# AP_AT42QT2120.net
KiCad netlist of a schematic drawn in EAGLE
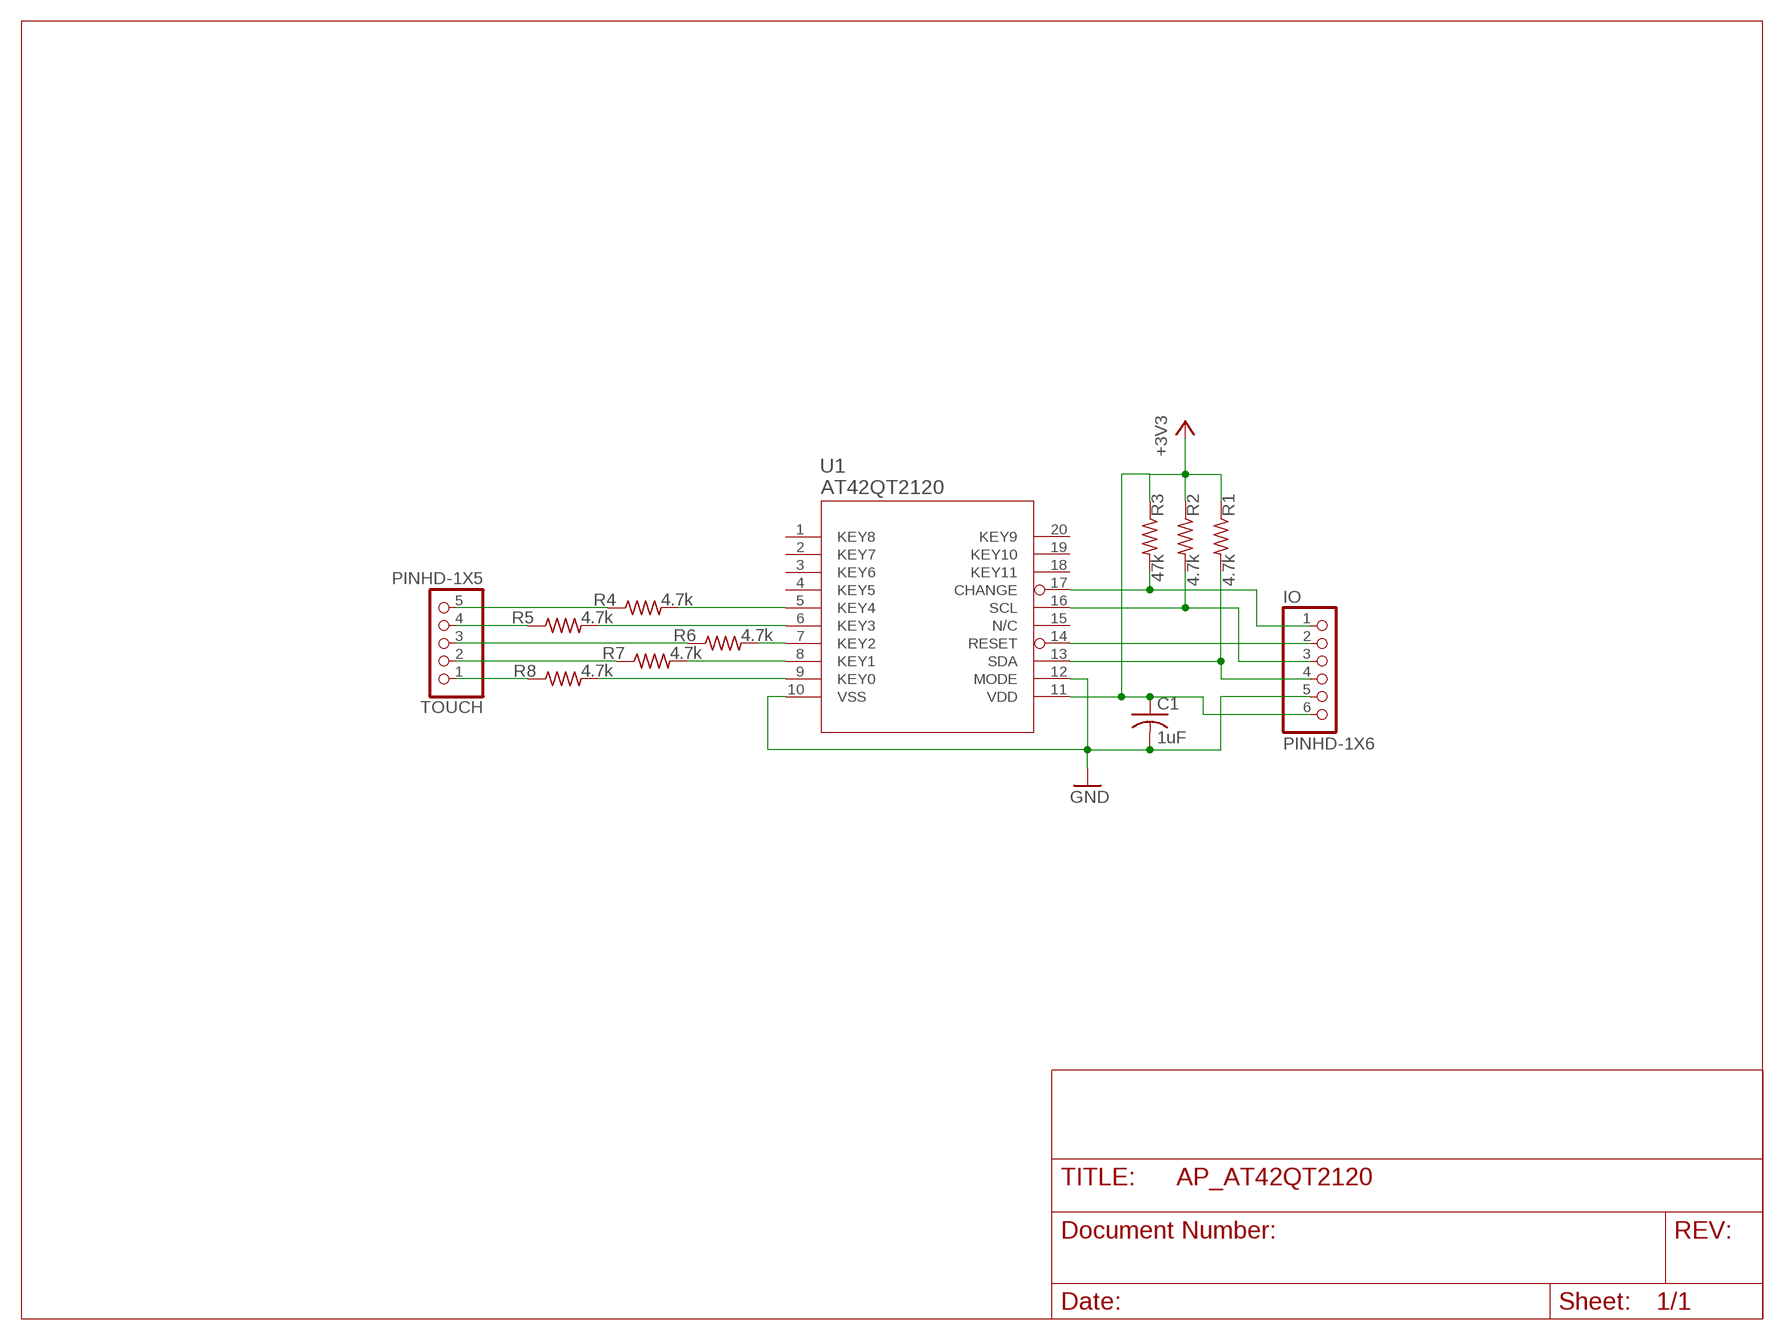
[diagram p0: schematic, sheet 1]

(export (version "E")
  (design (tool "Eeschema 10.0.6"))
  (components
    (comp (ref "C1")
      (value "1uF")
      (footprint "eagle-import:C1206")
      (libsource (lib "eagle-import") (part "C-USC1206"))
    )
    (comp (ref "IO")
      (value "PINHD-1X6")
      (footprint "eagle-import:1X06")
      (libsource (lib "eagle-import") (part "PINHD-1X6"))
    )
    (comp (ref "R1")
      (value "4.7k")
      (footprint "eagle-import:R1206")
      (libsource (lib "eagle-import") (part "R-US_R1206"))
    )
    (comp (ref "R2")
      (value "4.7k")
      (footprint "eagle-import:R1206")
      (libsource (lib "eagle-import") (part "R-US_R1206"))
    )
    (comp (ref "R3")
      (value "47k")
      (footprint "eagle-import:R1206")
      (libsource (lib "eagle-import") (part "R-US_R1206"))
    )
    (comp (ref "R4")
      (value "4.7k")
      (footprint "eagle-import:R1206")
      (libsource (lib "eagle-import") (part "R-US_R1206"))
    )
    (comp (ref "R5")
      (value "4.7k")
      (footprint "eagle-import:R1206")
      (libsource (lib "eagle-import") (part "R-US_R1206"))
    )
    (comp (ref "R6")
      (value "4.7k")
      (footprint "eagle-import:R1206")
      (libsource (lib "eagle-import") (part "R-US_R1206"))
    )
    (comp (ref "R7")
      (value "4.7k")
      (footprint "eagle-import:R1206")
      (libsource (lib "eagle-import") (part "R-US_R1206"))
    )
    (comp (ref "R8")
      (value "4.7k")
      (footprint "eagle-import:R1206")
      (libsource (lib "eagle-import") (part "R-US_R1206"))
    )
    (comp (ref "TOUCH")
      (value "PINHD-1X5")
      (footprint "eagle-import:1X05")
      (libsource (lib "eagle-import") (part "PINHD-1X5"))
    )
    (comp (ref "U1")
      (value "AT42QT2120")
      (footprint "eagle-import:SOIC20")
      (libsource (lib "eagle-import") (part "AT42QT2120-SU"))
    )
  )
  (nets
    (net (code "1") (name "+3V3") (class "Default")
      (node (ref "C1") (pin "1") (pinfunction "1_1") (pintype "passive"))
      (node (ref "IO") (pin "6") (pinfunction "6_6") (pintype "passive"))
      (node (ref "R1") (pin "1") (pinfunction "1_1") (pintype "passive"))
      (node (ref "R2") (pin "1") (pinfunction "1_1") (pintype "passive"))
      (node (ref "R3") (pin "1") (pinfunction "1_1") (pintype "passive"))
      (node (ref "U1") (pin "11") (pinfunction "VDD_11") (pintype "power_in"))
    )
    (net (code "2") (name "GND") (class "Default")
      (node (ref "C1") (pin "2") (pinfunction "2_2") (pintype "passive"))
      (node (ref "IO") (pin "5") (pinfunction "5_5") (pintype "passive"))
      (node (ref "U1") (pin "10") (pinfunction "VSS_10") (pintype "passive"))
      (node (ref "U1") (pin "12") (pinfunction "MODE_12") (pintype "passive"))
    )
    (net (code "3") (name "Net-(R4-Pad1)") (class "Default")
      (node (ref "R4") (pin "1") (pinfunction "1_1") (pintype "passive"))
      (node (ref "TOUCH") (pin "5") (pinfunction "5_5") (pintype "passive"))
    )
    (net (code "4") (name "Net-(R5-Pad1)") (class "Default")
      (node (ref "R5") (pin "1") (pinfunction "1_1") (pintype "passive"))
      (node (ref "TOUCH") (pin "4") (pinfunction "4_4") (pintype "passive"))
    )
    (net (code "5") (name "Net-(R6-Pad1)") (class "Default")
      (node (ref "R6") (pin "1") (pinfunction "1_1") (pintype "passive"))
      (node (ref "TOUCH") (pin "3") (pinfunction "3_3") (pintype "passive"))
    )
    (net (code "6") (name "Net-(R7-Pad1)") (class "Default")
      (node (ref "R7") (pin "1") (pinfunction "1_1") (pintype "passive"))
      (node (ref "TOUCH") (pin "2") (pinfunction "2_2") (pintype "passive"))
    )
    (net (code "7") (name "Net-(R8-Pad1)") (class "Default")
      (node (ref "R8") (pin "1") (pinfunction "1_1") (pintype "passive"))
      (node (ref "TOUCH") (pin "1") (pinfunction "1_1") (pintype "passive"))
    )
    (net (code "8") (name "Net-(U1-CHANGE)") (class "Default")
      (node (ref "IO") (pin "1") (pinfunction "1_1") (pintype "passive"))
      (node (ref "R3") (pin "2") (pinfunction "2_2") (pintype "passive"))
      (node (ref "U1") (pin "17") (pinfunction "CHANGE_17") (pintype "input"))
    )
    (net (code "9") (name "Net-(U1-KEY0)") (class "Default")
      (node (ref "R8") (pin "2") (pinfunction "2_2") (pintype "passive"))
      (node (ref "U1") (pin "9") (pinfunction "KEY0_9") (pintype "bidirectional"))
    )
    (net (code "10") (name "Net-(U1-KEY1)") (class "Default")
      (node (ref "R7") (pin "2") (pinfunction "2_2") (pintype "passive"))
      (node (ref "U1") (pin "8") (pinfunction "KEY1_8") (pintype "bidirectional"))
    )
    (net (code "11") (name "Net-(U1-KEY2)") (class "Default")
      (node (ref "R6") (pin "2") (pinfunction "2_2") (pintype "passive"))
      (node (ref "U1") (pin "7") (pinfunction "KEY2_7") (pintype "bidirectional"))
    )
    (net (code "12") (name "Net-(U1-KEY3)") (class "Default")
      (node (ref "R5") (pin "2") (pinfunction "2_2") (pintype "passive"))
      (node (ref "U1") (pin "6") (pinfunction "KEY3_6") (pintype "bidirectional"))
    )
    (net (code "13") (name "Net-(U1-KEY4)") (class "Default")
      (node (ref "R4") (pin "2") (pinfunction "2_2") (pintype "passive"))
      (node (ref "U1") (pin "5") (pinfunction "KEY4_5") (pintype "bidirectional"))
    )
    (net (code "14") (name "Net-(U1-RESET)") (class "Default")
      (node (ref "IO") (pin "2") (pinfunction "2_2") (pintype "passive"))
      (node (ref "U1") (pin "14") (pinfunction "RESET_14") (pintype "passive"))
    )
    (net (code "15") (name "Net-(U1-SCL)") (class "Default")
      (node (ref "IO") (pin "3") (pinfunction "3_3") (pintype "passive"))
      (node (ref "R2") (pin "2") (pinfunction "2_2") (pintype "passive"))
      (node (ref "U1") (pin "16") (pinfunction "SCL_16") (pintype "bidirectional"))
    )
    (net (code "16") (name "Net-(U1-SDA)") (class "Default")
      (node (ref "IO") (pin "4") (pinfunction "4_4") (pintype "passive"))
      (node (ref "R1") (pin "2") (pinfunction "2_2") (pintype "passive"))
      (node (ref "U1") (pin "13") (pinfunction "SDA_13") (pintype "bidirectional"))
    )
    (net (code "17") (name "unconnected-(U1-KEY5-Pad4)") (class "Default")
      (node (ref "U1") (pin "4") (pinfunction "KEY5_4") (pintype "bidirectional"))
    )
    (net (code "18") (name "unconnected-(U1-KEY6-Pad3)") (class "Default")
      (node (ref "U1") (pin "3") (pinfunction "KEY6_3") (pintype "bidirectional"))
    )
    (net (code "19") (name "unconnected-(U1-KEY7-Pad2)") (class "Default")
      (node (ref "U1") (pin "2") (pinfunction "KEY7_2") (pintype "bidirectional"))
    )
    (net (code "20") (name "unconnected-(U1-KEY8-Pad1)") (class "Default")
      (node (ref "U1") (pin "1") (pinfunction "KEY8_1") (pintype "bidirectional"))
    )
    (net (code "21") (name "unconnected-(U1-KEY9-Pad20)") (class "Default")
      (node (ref "U1") (pin "20") (pinfunction "KEY9_20") (pintype "bidirectional"))
    )
    (net (code "22") (name "unconnected-(U1-KEY10-Pad19)") (class "Default")
      (node (ref "U1") (pin "19") (pinfunction "KEY10_19") (pintype "bidirectional"))
    )
    (net (code "23") (name "unconnected-(U1-KEY11-Pad18)") (class "Default")
      (node (ref "U1") (pin "18") (pinfunction "KEY11_18") (pintype "bidirectional"))
    )
    (net (code "24") (name "unconnected-(U1-N{slash}C-Pad15)") (class "Default")
      (node (ref "U1") (pin "15") (pinfunction "N/C_15") (pintype "no_connect"))
    )
  )
)
